# Lithium_Battery_UVP_Switch.net
KiCad netlist of a schematic drawn in Altium Designer
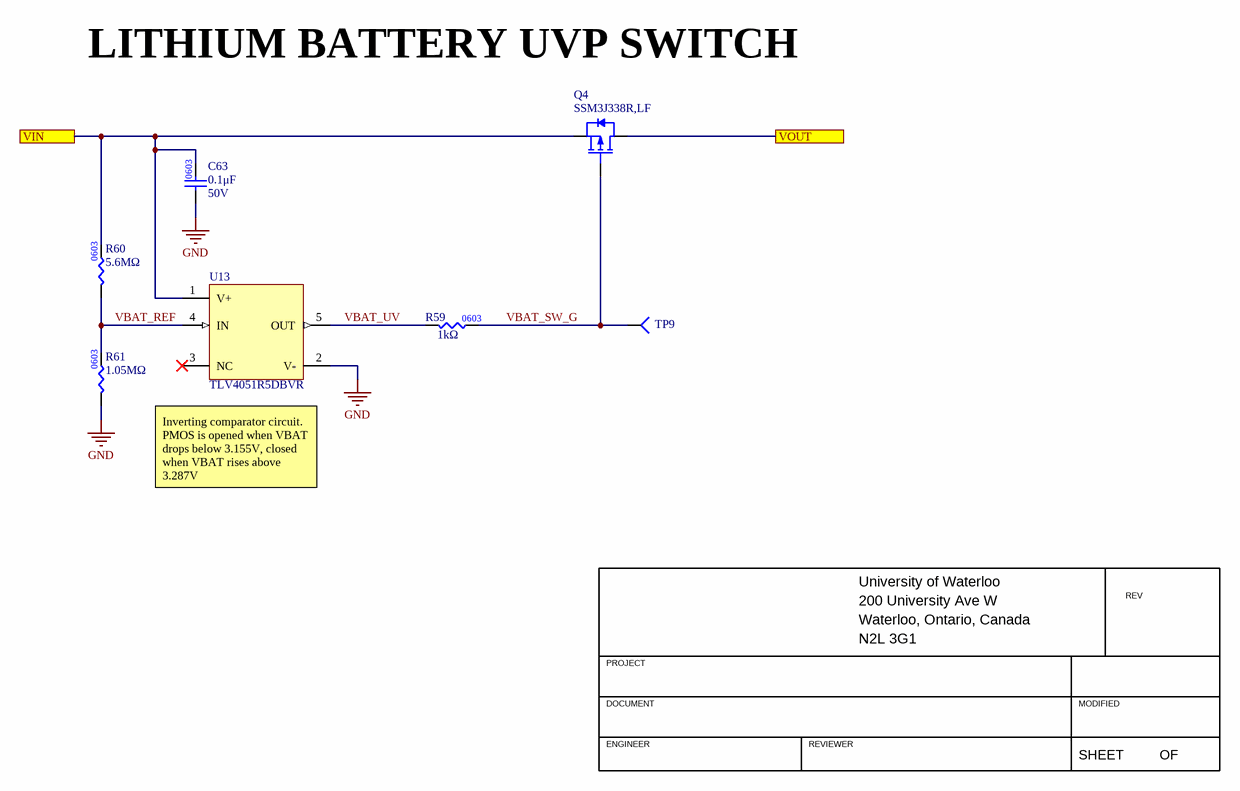
[diagram p0: Lithium Battery UVP Switch.SchDoc]

(export (version "E")
  (design (tool "Eeschema 10.0.6"))
  (components
    (comp (ref "C63")
      (value "0.1μF")
      (footprint "CAP0603")
      (description "CAP CER 0.1UF 50V X7R 0603")
      (fields (field (name "VOLTAGE RATING") "50V") (field (name "Comment") "CAP_0.1uF_50V_0603"))
      (libsource (lib "Personal_Schematic_Library_2022") (part "CAP_0.1uF_50V_0603"))
    )
    (comp (ref "Q4")
      (value "PMOS_12V_6A")
      (footprint "DIO-INC_SOT23")
      (description "MOSFET P-CH 12V 6A SOT23F")
      (fields (field (name "MANUFACTURER PART NUMBER 1") "SSM3J338R,LF"))
      (libsource (lib "Personal_Schematic_Library_2022") (part "PMOS_12V_6A"))
    )
    (comp (ref "R59")
      (value "1kΩ")
      (footprint "RES0603")
      (description "RES 1K OHM 1% 1/8W 0603")
      (fields (field (name "Comment") "RES_1kΩ_0603_1%"))
      (libsource (lib "Personal_Schematic_Library_2022") (part "RES_1kΩ_0603_1%"))
    )
    (comp (ref "R60")
      (value "5.6MΩ")
      (footprint "RES0603")
      (description "RES SMD 5.6M OHM 1% 1/10W 0603")
      (fields (field (name "TOLERANCE") "1%") (field (name "Comment") "RES_5.6MΩ_0603_1%"))
      (libsource (lib "Personal_Schematic_Library_2022") (part "RES_5.6MΩ_0603_1%"))
    )
    (comp (ref "R61")
      (value "1.05MΩ")
      (footprint "RES0603")
      (description "RES SMD 1.05M OHM 1% 1/10W 0603")
      (fields (field (name "Comment") "RES_1.05MΩ_0603_1%"))
      (libsource (lib "Personal_Schematic_Library_2022") (part "RES_1.05MΩ_0603_1%"))
    )
    (comp (ref "TP9")
      (value "TESTPOINT_1MM_CIRCLE")
      (footprint "TESTPOINT_CIRCLE_1MM")
      (description "TESTPOINT 1MM CIRCLE")
      (libsource (lib "Personal_Schematic_Library_2022") (part "TESTPOINT_1MM_CIRCLE"))
    )
    (comp (ref "U13")
      (value "TLV4051R5DBVR")
      (footprint "TI_SOT23-5")
      (description "IC COMPARATOR 1 VOL REF SOT23-5")
      (fields (field (name "MANUFACTURER PART NUMBER 1") "TLV4051R5DBVR"))
      (libsource (lib "Personal_Schematic_Library_2022") (part "TLV4051R5DBVR"))
    )
  )
  (nets
    (net (code "1") (name "/VBAT_REF") (class "Default")
      (node (ref "R60") (pin "1") (pinfunction "1_1") (pintype "passive"))
      (node (ref "R61") (pin "2") (pinfunction "2_2") (pintype "passive"))
      (node (ref "U13") (pin "4") (pinfunction "IN_4") (pintype "input"))
    )
    (net (code "2") (name "/VBAT_SW_G") (class "Default")
      (node (ref "Q4") (pin "1") (pinfunction "Gate_1") (pintype "passive"))
      (node (ref "R59") (pin "2") (pinfunction "2_2") (pintype "passive"))
      (node (ref "TP9") (pin "1") (pinfunction "=value_1") (pintype "passive"))
    )
    (net (code "3") (name "/VBAT_UV") (class "Default")
      (node (ref "R59") (pin "1") (pinfunction "1_1") (pintype "passive"))
      (node (ref "U13") (pin "5") (pinfunction "OUT_5") (pintype "output"))
    )
    (net (code "4") (name "/VIN") (class "Default")
      (node (ref "C63") (pin "2") (pinfunction "2_2") (pintype "passive"))
      (node (ref "Q4") (pin "2") (pinfunction "Source_2") (pintype "passive"))
      (node (ref "R60") (pin "2") (pinfunction "2_2") (pintype "passive"))
      (node (ref "U13") (pin "1") (pinfunction "V+_1") (pintype "power_in"))
    )
    (net (code "5") (name "/VOUT") (class "Default")
      (node (ref "Q4") (pin "3") (pinfunction "Drain_3") (pintype "passive"))
    )
    (net (code "6") (name "GND") (class "Default")
      (node (ref "C63") (pin "1") (pinfunction "1_1") (pintype "passive"))
      (node (ref "R61") (pin "1") (pinfunction "1_1") (pintype "passive"))
      (node (ref "U13") (pin "2") (pinfunction "V-_2") (pintype "power_in"))
    )
    (net (code "7") (name "unconnected-(U13-NC-Pad3)") (class "Default")
      (node (ref "U13") (pin "3") (pinfunction "NC_3") (pintype "passive+no_connect"))
    )
  )
)
